# SystemControl.net
KiCad netlist of a schematic drawn in EAGLE
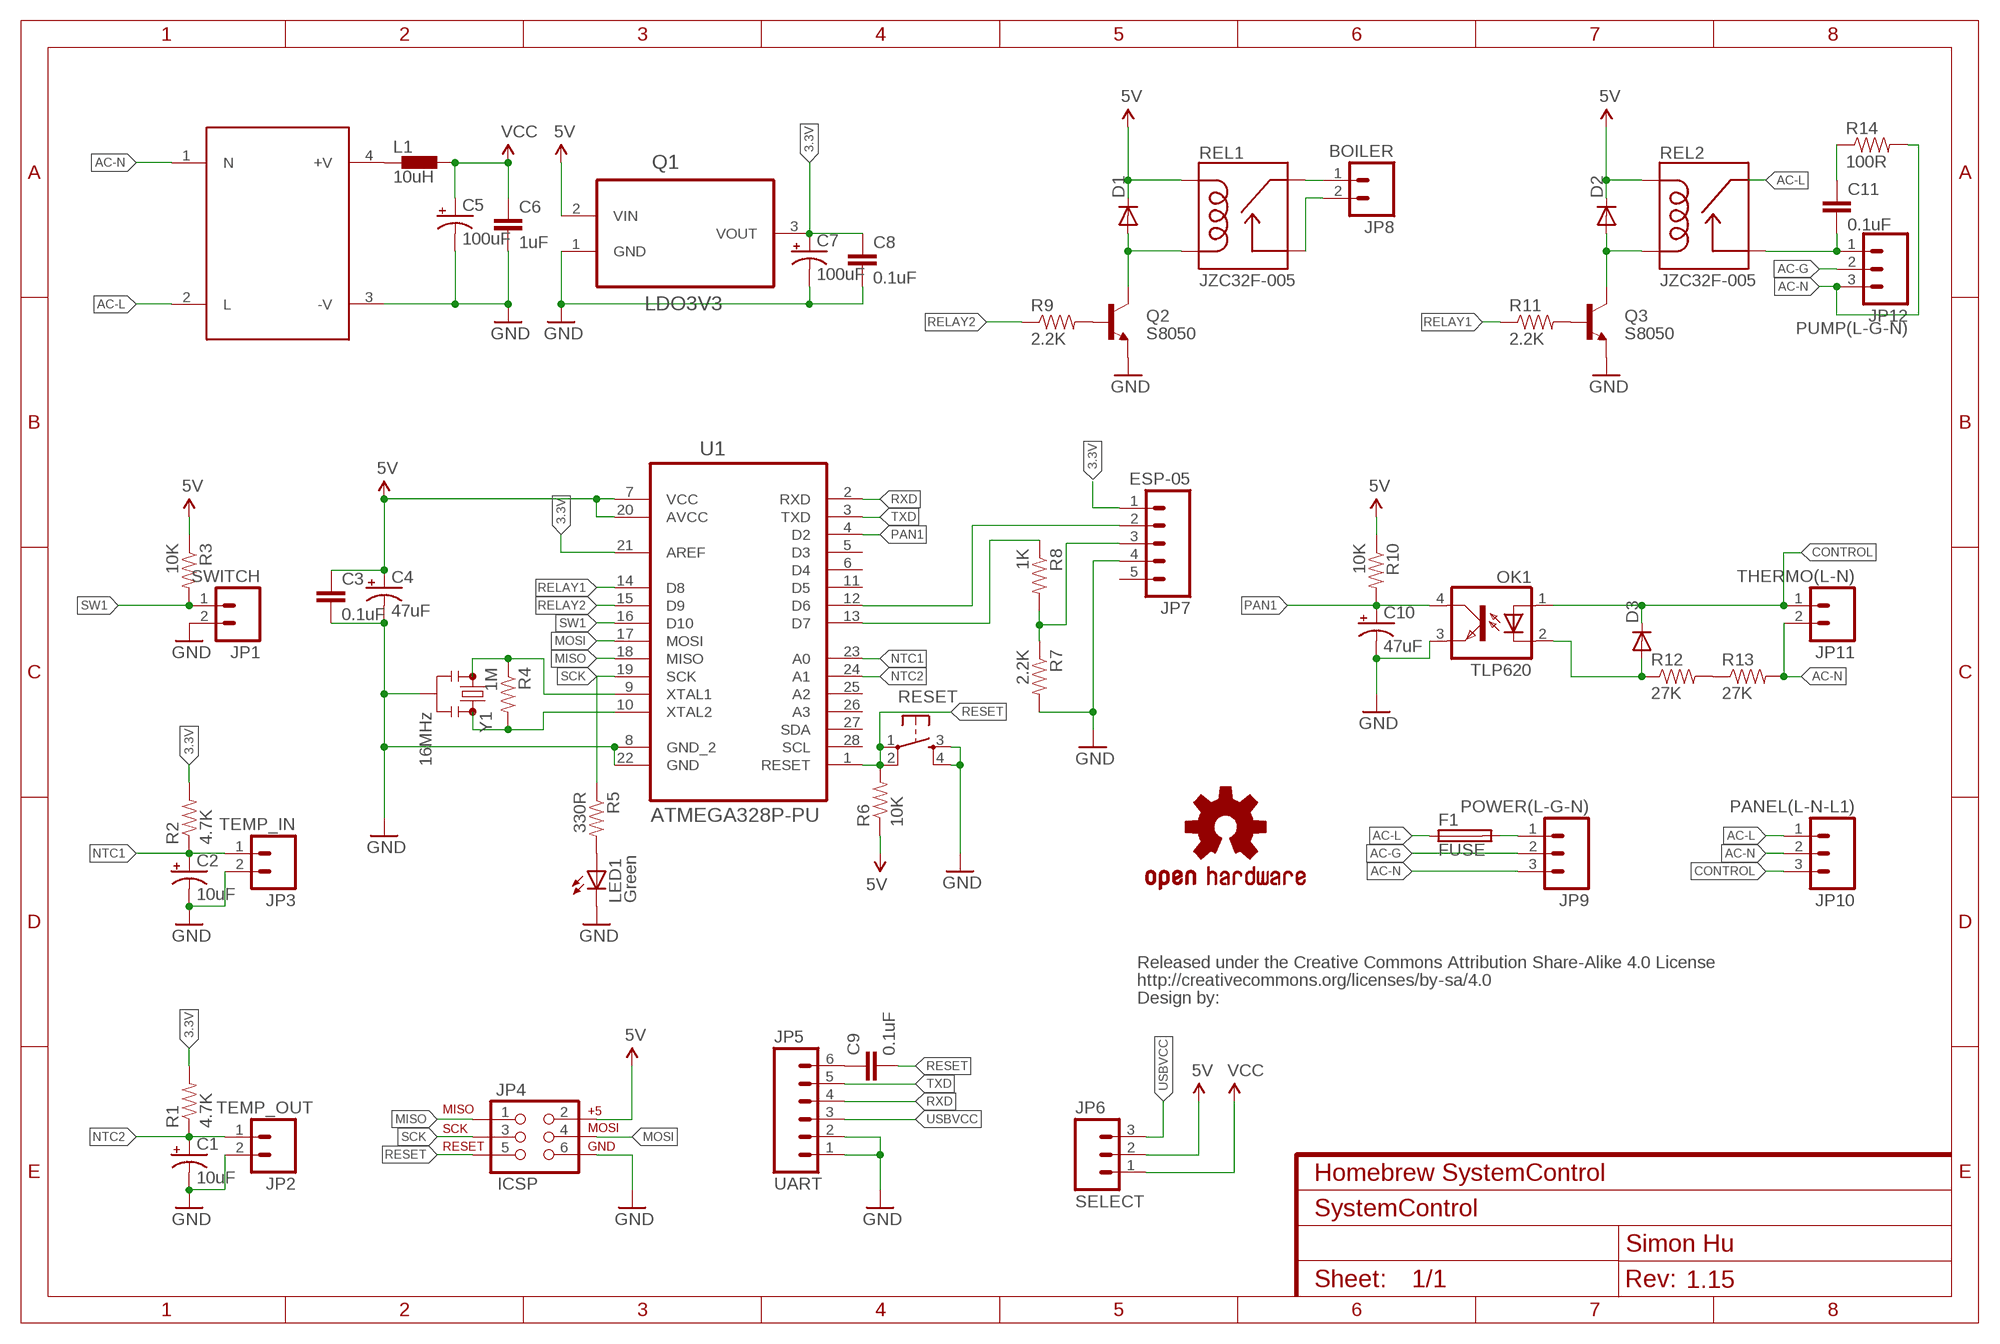
[diagram p0: schematic, sheet 1]

(export (version "E")
  (design (tool "Eeschema 10.0.6"))
  (components
    (comp (ref "C1")
      (value "10uF")
      (footprint "eagle-import:CPOL-RADIAL-10UF-25V")
      (libsource (lib "eagle-import") (part "CAP_POLPTH2"))
    )
    (comp (ref "C2")
      (value "10uF")
      (footprint "eagle-import:CPOL-RADIAL-10UF-25V")
      (libsource (lib "eagle-import") (part "CAP_POLPTH2"))
    )
    (comp (ref "C3")
      (value "0.1uF")
      (footprint "eagle-import:CAP-PTH-SMALL2")
      (libsource (lib "eagle-import") (part "CAPPTH2"))
    )
    (comp (ref "C4")
      (value "47uF")
      (footprint "eagle-import:CPOL-RADIAL-10UF-25V")
      (libsource (lib "eagle-import") (part "CAP_POLPTH2"))
    )
    (comp (ref "C5")
      (value "100uF")
      (footprint "eagle-import:CPOL-RADIAL-10UF-25V")
      (libsource (lib "eagle-import") (part "CAP_POLPTH2"))
    )
    (comp (ref "C6")
      (value "1uF")
      (footprint "eagle-import:CAP-PTH-SMALL2")
      (libsource (lib "eagle-import") (part "CAPPTH2"))
    )
    (comp (ref "C7")
      (value "100uF")
      (footprint "eagle-import:CPOL-RADIAL-10UF-25V")
      (libsource (lib "eagle-import") (part "CAP_POLPTH2"))
    )
    (comp (ref "C8")
      (value "0.1uF")
      (footprint "eagle-import:CAP-PTH-SMALL2")
      (libsource (lib "eagle-import") (part "CAPPTH2"))
    )
    (comp (ref "C9")
      (value "0.1uF")
      (footprint "eagle-import:CAP-PTH-SMALL2")
      (libsource (lib "eagle-import") (part "CAPPTH2"))
    )
    (comp (ref "C10")
      (value "47uF")
      (footprint "eagle-import:CPOL-RADIAL-10UF-25V")
      (libsource (lib "eagle-import") (part "CAP_POLPTH2"))
    )
    (comp (ref "C11")
      (value "0.1uF")
      (footprint "eagle-import:CAP-PTH-LARGE")
      (libsource (lib "eagle-import") (part "SparkFun-Passives_CAPPTH3"))
    )
    (comp (ref "CC_TEXT1")
      (value "CREATIVE_COMMONS")
      (footprint "eagle-import:CREATIVE_COMMONS")
      (libsource (lib "eagle-import") (part "CREATIVE_COMMONS"))
    )
    (comp (ref "D1")
      (value "1N4007")
      (footprint "eagle-import:DO-1N4148")
      (libsource (lib "eagle-import") (part "DIODEDO-1N4148"))
    )
    (comp (ref "D2")
      (value "1N4007")
      (footprint "eagle-import:DO-1N4148")
      (libsource (lib "eagle-import") (part "DIODEDO-1N4148"))
    )
    (comp (ref "D3")
      (value "1N4007")
      (footprint "eagle-import:DO-1N4148")
      (libsource (lib "eagle-import") (part "DIODEDO-1N4148"))
    )
    (comp (ref "F1")
      (value "FUSE")
      (footprint "eagle-import:SHK20L")
      (libsource (lib "eagle-import") (part "FUSESHK20L"))
    )
    (comp (ref "IC1")
      (value "NI-BOXING")
      (footprint "eagle-import:NI-BOXING")
      (libsource (lib "eagle-import") (part "NI-BOXING"))
    )
    (comp (ref "JP1")
      (value "SWITCH")
      (footprint "eagle-import:1X02_LOCK")
      (libsource (lib "eagle-import") (part "M02LOCK"))
    )
    (comp (ref "JP2")
      (value "TEMP_OUT")
      (footprint "eagle-import:1X02_LOCK")
      (libsource (lib "eagle-import") (part "M02LOCK"))
    )
    (comp (ref "JP3")
      (value "TEMP_IN")
      (footprint "eagle-import:1X02_LOCK")
      (libsource (lib "eagle-import") (part "M02LOCK"))
    )
    (comp (ref "JP4")
      (value "ICSP")
      (footprint "eagle-import:2X3")
      (libsource (lib "eagle-import") (part "AVR_SPI_PRG_6PTH"))
    )
    (comp (ref "JP5")
      (value "UART")
      (footprint "eagle-import:1X06_LOCK")
      (libsource (lib "eagle-import") (part "M06LOCK"))
    )
    (comp (ref "JP6")
      (value "SELECT")
      (footprint "eagle-import:1X03_LOCK")
      (libsource (lib "eagle-import") (part "M03LOCK"))
    )
    (comp (ref "JP7")
      (value "ESP-05")
      (footprint "eagle-import:1X05_LOCK")
      (libsource (lib "eagle-import") (part "M05LOCK"))
    )
    (comp (ref "JP8")
      (value "BOILER")
      (footprint "eagle-import:SCREWTERMINAL-5MM-2")
      (libsource (lib "eagle-import") (part "M025MM"))
    )
    (comp (ref "JP9")
      (value "POWER(L-G-N)")
      (footprint "eagle-import:SCREWTERMINAL-5MM-3")
      (libsource (lib "eagle-import") (part "M03-SCREW-5MM"))
    )
    (comp (ref "JP10")
      (value "PANEL(L-N-L1)")
      (footprint "eagle-import:SCREWTERMINAL-5MM-3")
      (libsource (lib "eagle-import") (part "M03-SCREW-5MM"))
    )
    (comp (ref "JP11")
      (value "THERMO(L-N)")
      (footprint "eagle-import:SCREWTERMINAL-5MM-2")
      (libsource (lib "eagle-import") (part "M025MM"))
    )
    (comp (ref "JP12")
      (value "PUMP(L-G-N)")
      (footprint "eagle-import:SCREWTERMINAL-5MM-3")
      (libsource (lib "eagle-import") (part "M03-SCREW-5MM"))
    )
    (comp (ref "L1")
      (value "10uH")
      (footprint "eagle-import:BL01RN1A")
      (libsource (lib "eagle-import") (part "BL01RN1A"))
    )
    (comp (ref "LED1")
      (value "Green")
      (footprint "eagle-import:LED3MM")
      (libsource (lib "eagle-import") (part "LED3MM"))
    )
    (comp (ref "LOGO1")
      (value "OSHW-LOGOL")
      (footprint "eagle-import:OSHW-LOGO-L")
      (libsource (lib "eagle-import") (part "OSHW-LOGOL"))
    )
    (comp (ref "OK1")
      (value "TLP620")
      (footprint "eagle-import:DIL04")
      (fields (field (name "MPN") "PC817X4J000F"))
      (libsource (lib "eagle-import") (part "PC817"))
    )
    (comp (ref "Q1")
      (value "LDO3V3")
      (footprint "eagle-import:TO127P254X533-3")
      (fields (field (name "MPN") "MCP1702-3302E/TO"))
      (libsource (lib "eagle-import") (part "MCP1702-3302E/TO"))
    )
    (comp (ref "Q2")
      (value "S8050")
      (footprint "eagle-import:TO-92")
      (libsource (lib "eagle-import") (part "TRANSISTOR_NPN2N3904"))
    )
    (comp (ref "Q3")
      (value "S8050")
      (footprint "eagle-import:TO-92")
      (libsource (lib "eagle-import") (part "TRANSISTOR_NPN2N3904"))
    )
    (comp (ref "R1")
      (value "4.7K")
      (footprint "eagle-import:AXIAL-0.4")
      (libsource (lib "eagle-import") (part "RESISTORPTH-1/4W"))
    )
    (comp (ref "R2")
      (value "4.7K")
      (footprint "eagle-import:AXIAL-0.4")
      (libsource (lib "eagle-import") (part "RESISTORPTH-1/4W"))
    )
    (comp (ref "R3")
      (value "10K")
      (footprint "eagle-import:AXIAL-0.4")
      (libsource (lib "eagle-import") (part "RESISTORPTH-1/4W"))
    )
    (comp (ref "R4")
      (value "1M")
      (footprint "eagle-import:AXIAL-0.4")
      (libsource (lib "eagle-import") (part "RESISTORPTH-1/4W"))
    )
    (comp (ref "R5")
      (value "330R")
      (footprint "eagle-import:AXIAL-0.4")
      (libsource (lib "eagle-import") (part "RESISTORPTH-1/4W"))
    )
    (comp (ref "R6")
      (value "10K")
      (footprint "eagle-import:AXIAL-0.4")
      (libsource (lib "eagle-import") (part "RESISTORPTH-1/4W"))
    )
    (comp (ref "R7")
      (value "2.2K")
      (footprint "eagle-import:AXIAL-0.4")
      (libsource (lib "eagle-import") (part "RESISTORPTH-1/4W"))
    )
    (comp (ref "R8")
      (value "1K")
      (footprint "eagle-import:AXIAL-0.4")
      (libsource (lib "eagle-import") (part "RESISTORPTH-1/4W"))
    )
    (comp (ref "R9")
      (value "2.2K")
      (footprint "eagle-import:AXIAL-0.4")
      (libsource (lib "eagle-import") (part "RESISTORPTH-1/4W"))
    )
    (comp (ref "R10")
      (value "10K")
      (footprint "eagle-import:AXIAL-0.4")
      (libsource (lib "eagle-import") (part "RESISTORPTH-1/4W"))
    )
    (comp (ref "R11")
      (value "2.2K")
      (footprint "eagle-import:AXIAL-0.4")
      (libsource (lib "eagle-import") (part "RESISTORPTH-1/4W"))
    )
    (comp (ref "R12")
      (value "27K")
      (footprint "eagle-import:AXIAL-0.6")
      (libsource (lib "eagle-import") (part "SparkFun-Resistors_RESISTORPTH-1W"))
    )
    (comp (ref "R13")
      (value "27K")
      (footprint "eagle-import:AXIAL-0.6")
      (libsource (lib "eagle-import") (part "SparkFun-Resistors_RESISTORPTH-1W"))
    )
    (comp (ref "R14")
      (value "100R")
      (footprint "eagle-import:AXIAL-0.6")
      (libsource (lib "eagle-import") (part "SparkFun-Resistors_RESISTORPTH-1W"))
    )
    (comp (ref "REL1")
      (value "JZC32F-005")
      (footprint "eagle-import:RELAY-JZC")
      (libsource (lib "eagle-import") (part "RELAYPTH4"))
    )
    (comp (ref "REL2")
      (value "JZC32F-005")
      (footprint "eagle-import:RELAY-JZC")
      (libsource (lib "eagle-import") (part "RELAYPTH4"))
    )
    (comp (ref "RESET")
      (value "TAC_SWITCHPTH")
      (footprint "eagle-import:TACTILE-PTH")
      (libsource (lib "eagle-import") (part "TAC_SWITCHPTH"))
    )
    (comp (ref "U1")
      (value "ATMEGA328P-PU")
      (footprint "eagle-import:DIP254P762X457-28")
      (libsource (lib "eagle-import") (part "ATMEGA328P-PU"))
    )
    (comp (ref "Y1")
      (value "16MHz")
      (footprint "eagle-import:RESONATOR-PTH")
      (libsource (lib "eagle-import") (part "RESONATORPTH"))
    )
  )
  (nets
    (net (code "1") (name "3.3V") (class "Default")
      (node (ref "C7") (pin "1") (pinfunction "+_1") (pintype "passive"))
      (node (ref "C8") (pin "1") (pinfunction "1_1") (pintype "passive"))
      (node (ref "JP7") (pin "1") (pinfunction "1_1") (pintype "passive"))
      (node (ref "Q1") (pin "3") (pinfunction "VOUT_3") (pintype "output"))
      (node (ref "R1") (pin "P$2") (pinfunction "2_P$2") (pintype "passive"))
      (node (ref "R2") (pin "P$2") (pinfunction "2_P$2") (pintype "passive"))
      (node (ref "U1") (pin "21") (pinfunction "AREF_21") (pintype "input"))
    )
    (net (code "2") (name "5V") (class "Default")
      (node (ref "C3") (pin "1") (pinfunction "1_1") (pintype "passive"))
      (node (ref "C4") (pin "1") (pinfunction "+_1") (pintype "passive"))
      (node (ref "D1") (pin "C") (pinfunction "C_C") (pintype "passive"))
      (node (ref "D2") (pin "C") (pinfunction "C_C") (pintype "passive"))
      (node (ref "JP4") (pin "2") (pinfunction "VCC_2") (pintype "passive"))
      (node (ref "JP6") (pin "2") (pinfunction "2_2") (pintype "passive"))
      (node (ref "Q1") (pin "2") (pinfunction "VIN_2") (pintype "input"))
      (node (ref "R10") (pin "P$1") (pinfunction "1_P$1") (pintype "passive"))
      (node (ref "R3") (pin "P$1") (pinfunction "1_P$1") (pintype "passive"))
      (node (ref "R6") (pin "P$1") (pinfunction "1_P$1") (pintype "passive"))
      (node (ref "REL1") (pin "5") (pinfunction "COIL1_5") (pintype "bidirectional"))
      (node (ref "REL2") (pin "5") (pinfunction "COIL1_5") (pintype "bidirectional"))
      (node (ref "U1") (pin "20") (pinfunction "AVCC_20") (pintype "power_in"))
      (node (ref "U1") (pin "7") (pinfunction "VCC_7") (pintype "power_in"))
    )
    (net (code "3") (name "AC-G") (class "Default")
      (node (ref "JP12") (pin "2") (pinfunction "2_2") (pintype "passive"))
      (node (ref "JP9") (pin "2") (pinfunction "2_2") (pintype "passive"))
    )
    (net (code "4") (name "AC-L") (class "Default")
      (node (ref "F1") (pin "1A") (pinfunction "1_1A") (pintype "passive"))
      (node (ref "IC1") (pin "2") (pinfunction "L_2") (pintype "bidirectional"))
      (node (ref "JP10") (pin "1") (pinfunction "1_1") (pintype "passive"))
      (node (ref "REL2") (pin "4") (pinfunction "MAIN_4") (pintype "bidirectional"))
    )
    (net (code "5") (name "AC-N") (class "Default")
      (node (ref "IC1") (pin "1") (pinfunction "N_1") (pintype "bidirectional"))
      (node (ref "JP10") (pin "2") (pinfunction "2_2") (pintype "passive"))
      (node (ref "JP11") (pin "2") (pinfunction "2_2") (pintype "passive"))
      (node (ref "JP12") (pin "3") (pinfunction "3_3") (pintype "passive"))
      (node (ref "JP9") (pin "3") (pinfunction "3_3") (pintype "passive"))
      (node (ref "R13") (pin "P$2") (pinfunction "2_P$2") (pintype "passive"))
      (node (ref "R14") (pin "P$2") (pinfunction "2_P$2") (pintype "passive"))
    )
    (net (code "6") (name "CONTROL") (class "Default")
      (node (ref "D3") (pin "C") (pinfunction "C_C") (pintype "passive"))
      (node (ref "JP10") (pin "3") (pinfunction "3_3") (pintype "passive"))
      (node (ref "JP11") (pin "1") (pinfunction "1_1") (pintype "passive"))
      (node (ref "OK1") (pin "1") (pinfunction "A_1") (pintype "passive"))
    )
    (net (code "7") (name "GND") (class "Default")
      (node (ref "C1") (pin "2") (pinfunction "-_2") (pintype "passive"))
      (node (ref "C10") (pin "2") (pinfunction "-_2") (pintype "passive"))
      (node (ref "C2") (pin "2") (pinfunction "-_2") (pintype "passive"))
      (node (ref "C3") (pin "2") (pinfunction "2_2") (pintype "passive"))
      (node (ref "C4") (pin "2") (pinfunction "-_2") (pintype "passive"))
      (node (ref "C5") (pin "2") (pinfunction "-_2") (pintype "passive"))
      (node (ref "C6") (pin "2") (pinfunction "2_2") (pintype "passive"))
      (node (ref "C7") (pin "2") (pinfunction "-_2") (pintype "passive"))
      (node (ref "C8") (pin "2") (pinfunction "2_2") (pintype "passive"))
      (node (ref "IC1") (pin "3") (pinfunction "-V_3") (pintype "bidirectional"))
      (node (ref "JP1") (pin "2") (pinfunction "2_2") (pintype "passive"))
      (node (ref "JP2") (pin "2") (pinfunction "2_2") (pintype "passive"))
      (node (ref "JP3") (pin "2") (pinfunction "2_2") (pintype "passive"))
      (node (ref "JP4") (pin "6") (pinfunction "GND_6") (pintype "passive"))
      (node (ref "JP5") (pin "1") (pinfunction "GND_1") (pintype "passive"))
      (node (ref "JP5") (pin "2") (pinfunction "EMPTY_2") (pintype "passive"))
      (node (ref "JP7") (pin "4") (pinfunction "4_4") (pintype "passive"))
      (node (ref "LED1") (pin "K") (pinfunction "C_K") (pintype "passive"))
      (node (ref "OK1") (pin "3") (pinfunction "EMIT_3") (pintype "passive"))
      (node (ref "Q1") (pin "1") (pinfunction "GND_1") (pintype "passive"))
      (node (ref "Q2") (pin "1") (pinfunction "E_1") (pintype "passive"))
      (node (ref "Q3") (pin "1") (pinfunction "E_1") (pintype "passive"))
      (node (ref "R7") (pin "P$2") (pinfunction "2_P$2") (pintype "passive"))
      (node (ref "RESET") (pin "3") (pinfunction "3_3") (pintype "passive"))
      (node (ref "RESET") (pin "4") (pinfunction "4_4") (pintype "passive"))
      (node (ref "U1") (pin "22") (pinfunction "GND_22") (pintype "passive"))
      (node (ref "U1") (pin "8") (pinfunction "GND_2_8") (pintype "passive"))
      (node (ref "Y1") (pin "2") (pinfunction "2_2") (pintype "passive"))
    )
    (net (code "8") (name "MISO") (class "Default")
      (node (ref "JP4") (pin "1") (pinfunction "MISO_1") (pintype "passive"))
      (node (ref "U1") (pin "18") (pinfunction "MISO_18") (pintype "bidirectional"))
    )
    (net (code "9") (name "MOSI") (class "Default")
      (node (ref "JP4") (pin "4") (pinfunction "MOSI_4") (pintype "passive"))
      (node (ref "U1") (pin "17") (pinfunction "MOSI_17") (pintype "bidirectional"))
    )
    (net (code "10") (name "NTC1") (class "Default")
      (node (ref "C2") (pin "1") (pinfunction "+_1") (pintype "passive"))
      (node (ref "JP3") (pin "1") (pinfunction "1_1") (pintype "passive"))
      (node (ref "R2") (pin "P$1") (pinfunction "1_P$1") (pintype "passive"))
      (node (ref "U1") (pin "23") (pinfunction "A0_23") (pintype "bidirectional"))
    )
    (net (code "11") (name "NTC2") (class "Default")
      (node (ref "C1") (pin "1") (pinfunction "+_1") (pintype "passive"))
      (node (ref "JP2") (pin "1") (pinfunction "1_1") (pintype "passive"))
      (node (ref "R1") (pin "P$1") (pinfunction "1_P$1") (pintype "passive"))
      (node (ref "U1") (pin "24") (pinfunction "A1_24") (pintype "bidirectional"))
    )
    (net (code "12") (name "Net-(F1-2)") (class "Default")
      (node (ref "F1") (pin "2A") (pinfunction "2_2A") (pintype "passive"))
      (node (ref "JP9") (pin "1") (pinfunction "1_1") (pintype "passive"))
    )
    (net (code "13") (name "Net-(IC1-+V)") (class "Default")
      (node (ref "IC1") (pin "4") (pinfunction "+V_4") (pintype "bidirectional"))
      (node (ref "L1") (pin "1") (pinfunction "1_1") (pintype "passive"))
    )
    (net (code "14") (name "Net-(JP5-RESET)") (class "Default")
      (node (ref "C9") (pin "1") (pinfunction "1_1") (pintype "passive"))
      (node (ref "JP5") (pin "6") (pinfunction "RESET_6") (pintype "passive"))
    )
    (net (code "15") (name "Net-(OK1-C)") (class "Default")
      (node (ref "D3") (pin "A") (pinfunction "A_A") (pintype "passive"))
      (node (ref "OK1") (pin "2") (pinfunction "C_2") (pintype "passive"))
      (node (ref "R12") (pin "P$1") (pinfunction "1_P$1") (pintype "passive"))
    )
    (net (code "16") (name "Net-(Q2-B)") (class "Default")
      (node (ref "Q2") (pin "2") (pinfunction "B_2") (pintype "passive"))
      (node (ref "R9") (pin "P$2") (pinfunction "2_P$2") (pintype "passive"))
    )
    (net (code "17") (name "Net-(Q2-C)") (class "Default")
      (node (ref "D1") (pin "A") (pinfunction "A_A") (pintype "passive"))
      (node (ref "Q2") (pin "3") (pinfunction "C_3") (pintype "passive"))
      (node (ref "REL1") (pin "1") (pinfunction "COIL2_1") (pintype "bidirectional"))
    )
    (net (code "18") (name "Net-(Q3-B)") (class "Default")
      (node (ref "Q3") (pin "2") (pinfunction "B_2") (pintype "passive"))
      (node (ref "R11") (pin "P$2") (pinfunction "2_P$2") (pintype "passive"))
    )
    (net (code "19") (name "Net-(Q3-C)") (class "Default")
      (node (ref "D2") (pin "A") (pinfunction "A_A") (pintype "passive"))
      (node (ref "Q3") (pin "3") (pinfunction "C_3") (pintype "passive"))
      (node (ref "REL2") (pin "1") (pinfunction "COIL2_1") (pintype "bidirectional"))
    )
    (net (code "20") (name "Net-(R4-1)") (class "Default")
      (node (ref "R4") (pin "P$1") (pinfunction "1_P$1") (pintype "passive"))
      (node (ref "U1") (pin "9") (pinfunction "XTAL1_9") (pintype "bidirectional"))
      (node (ref "Y1") (pin "1") (pinfunction "1_1") (pintype "passive"))
    )
    (net (code "21") (name "Net-(R4-2)") (class "Default")
      (node (ref "R4") (pin "P$2") (pinfunction "2_P$2") (pintype "passive"))
      (node (ref "U1") (pin "10") (pinfunction "XTAL2_10") (pintype "bidirectional"))
      (node (ref "Y1") (pin "3") (pinfunction "3_3") (pintype "passive"))
    )
    (net (code "22") (name "Net-(R5-2)") (class "Default")
      (node (ref "LED1") (pin "A") (pinfunction "A_A") (pintype "passive"))
      (node (ref "R5") (pin "P$2") (pinfunction "2_P$2") (pintype "passive"))
    )
    (net (code "23") (name "Net-(R7-1)") (class "Default")
      (node (ref "JP7") (pin "3") (pinfunction "3_3") (pintype "passive"))
      (node (ref "R7") (pin "P$1") (pinfunction "1_P$1") (pintype "passive"))
      (node (ref "R8") (pin "P$2") (pinfunction "2_P$2") (pintype "passive"))
    )
    (net (code "24") (name "Net-(R8-1)") (class "Default")
      (node (ref "R8") (pin "P$1") (pinfunction "1_P$1") (pintype "passive"))
      (node (ref "U1") (pin "13") (pinfunction "D7_13") (pintype "bidirectional"))
    )
    (net (code "25") (name "Net-(R12-2)") (class "Default")
      (node (ref "R12") (pin "P$2") (pinfunction "2_P$2") (pintype "passive"))
      (node (ref "R13") (pin "P$1") (pinfunction "1_P$1") (pintype "passive"))
    )
    (net (code "26") (name "Net-(R14-1)") (class "Default")
      (node (ref "C11") (pin "1") (pinfunction "1_1") (pintype "passive"))
      (node (ref "R14") (pin "P$1") (pinfunction "1_P$1") (pintype "passive"))
    )
    (net (code "27") (name "Net-(REL1-MAIN)") (class "Default")
      (node (ref "JP8") (pin "1") (pinfunction "1_1") (pintype "passive"))
      (node (ref "REL1") (pin "4") (pinfunction "MAIN_4") (pintype "bidirectional"))
    )
    (net (code "28") (name "Net-(REL1-NO)") (class "Default")
      (node (ref "JP8") (pin "2") (pinfunction "2_2") (pintype "passive"))
      (node (ref "REL1") (pin "3") (pinfunction "NO_3") (pintype "bidirectional"))
    )
    (net (code "29") (name "Net-(REL2-NO)") (class "Default")
      (node (ref "C11") (pin "2") (pinfunction "2_2") (pintype "passive"))
      (node (ref "JP12") (pin "1") (pinfunction "1_1") (pintype "passive"))
      (node (ref "REL2") (pin "3") (pinfunction "NO_3") (pintype "bidirectional"))
    )
    (net (code "30") (name "Net-(U1-D6)") (class "Default")
      (node (ref "JP7") (pin "2") (pinfunction "2_2") (pintype "passive"))
      (node (ref "U1") (pin "12") (pinfunction "D6_12") (pintype "bidirectional"))
    )
    (net (code "31") (name "PAN1") (class "Default")
      (node (ref "C10") (pin "1") (pinfunction "+_1") (pintype "passive"))
      (node (ref "OK1") (pin "4") (pinfunction "COL_4") (pintype "passive"))
      (node (ref "R10") (pin "P$2") (pinfunction "2_P$2") (pintype "passive"))
      (node (ref "U1") (pin "4") (pinfunction "D2_4") (pintype "bidirectional"))
    )
    (net (code "32") (name "RELAY1") (class "Default")
      (node (ref "R11") (pin "P$1") (pinfunction "1_P$1") (pintype "passive"))
      (node (ref "U1") (pin "14") (pinfunction "D8_14") (pintype "bidirectional"))
    )
    (net (code "33") (name "RELAY2") (class "Default")
      (node (ref "R9") (pin "P$1") (pinfunction "1_P$1") (pintype "passive"))
      (node (ref "U1") (pin "15") (pinfunction "D9_15") (pintype "bidirectional"))
    )
    (net (code "34") (name "RESET") (class "Default")
      (node (ref "C9") (pin "2") (pinfunction "2_2") (pintype "passive"))
      (node (ref "JP4") (pin "5") (pinfunction "RESET_5") (pintype "passive"))
      (node (ref "R6") (pin "P$2") (pinfunction "2_P$2") (pintype "passive"))
      (node (ref "RESET") (pin "1") (pinfunction "1_1") (pintype "passive"))
      (node (ref "RESET") (pin "2") (pinfunction "2_2") (pintype "passive"))
      (node (ref "U1") (pin "1") (pinfunction "RESET_1") (pintype "bidirectional"))
    )
    (net (code "35") (name "RXD") (class "Default")
      (node (ref "JP5") (pin "4") (pinfunction "RXD_4") (pintype "passive"))
      (node (ref "U1") (pin "2") (pinfunction "RXD_2") (pintype "bidirectional"))
    )
    (net (code "36") (name "SCK") (class "Default")
      (node (ref "JP4") (pin "3") (pinfunction "SCK_3") (pintype "passive"))
      (node (ref "R5") (pin "P$1") (pinfunction "1_P$1") (pintype "passive"))
      (node (ref "U1") (pin "19") (pinfunction "SCK_19") (pintype "bidirectional"))
    )
    (net (code "37") (name "SW1") (class "Default")
      (node (ref "JP1") (pin "1") (pinfunction "1_1") (pintype "passive"))
      (node (ref "R3") (pin "P$2") (pinfunction "2_P$2") (pintype "passive"))
      (node (ref "U1") (pin "16") (pinfunction "D10_16") (pintype "bidirectional"))
    )
    (net (code "38") (name "TXD") (class "Default")
      (node (ref "JP5") (pin "5") (pinfunction "TXD_5") (pintype "passive"))
      (node (ref "U1") (pin "3") (pinfunction "TXD_3") (pintype "bidirectional"))
    )
    (net (code "39") (name "USBVCC") (class "Default")
      (node (ref "JP5") (pin "3") (pinfunction "VCC_3") (pintype "passive"))
      (node (ref "JP6") (pin "3") (pinfunction "3_3") (pintype "passive"))
    )
    (net (code "40") (name "VCC") (class "Default")
      (node (ref "C5") (pin "1") (pinfunction "+_1") (pintype "passive"))
      (node (ref "C6") (pin "1") (pinfunction "1_1") (pintype "passive"))
      (node (ref "JP6") (pin "1") (pinfunction "1_1") (pintype "passive"))
      (node (ref "L1") (pin "2") (pinfunction "2_2") (pintype "passive"))
    )
    (net (code "41") (name "unconnected-(JP7-Pad5)") (class "Default")
      (node (ref "JP7") (pin "5") (pinfunction "5_5") (pintype "passive"))
    )
    (net (code "42") (name "unconnected-(U1-A2-Pad25)") (class "Default")
      (node (ref "U1") (pin "25") (pinfunction "A2_25") (pintype "bidirectional"))
    )
    (net (code "43") (name "unconnected-(U1-A3-Pad26)") (class "Default")
      (node (ref "U1") (pin "26") (pinfunction "A3_26") (pintype "bidirectional"))
    )
    (net (code "44") (name "unconnected-(U1-D3-Pad5)") (class "Default")
      (node (ref "U1") (pin "5") (pinfunction "D3_5") (pintype "bidirectional"))
    )
    (net (code "45") (name "unconnected-(U1-D4-Pad6)") (class "Default")
      (node (ref "U1") (pin "6") (pinfunction "D4_6") (pintype "bidirectional"))
    )
    (net (code "46") (name "unconnected-(U1-D5-Pad11)") (class "Default")
      (node (ref "U1") (pin "11") (pinfunction "D5_11") (pintype "bidirectional"))
    )
    (net (code "47") (name "unconnected-(U1-SCL-Pad28)") (class "Default")
      (node (ref "U1") (pin "28") (pinfunction "SCL_28") (pintype "bidirectional"))
    )
    (net (code "48") (name "unconnected-(U1-SDA-Pad27)") (class "Default")
      (node (ref "U1") (pin "27") (pinfunction "SDA_27") (pintype "bidirectional"))
    )
  )
)
